# circuit_de_charge.net
KiCad netlist of a schematic drawn in Altium Designer
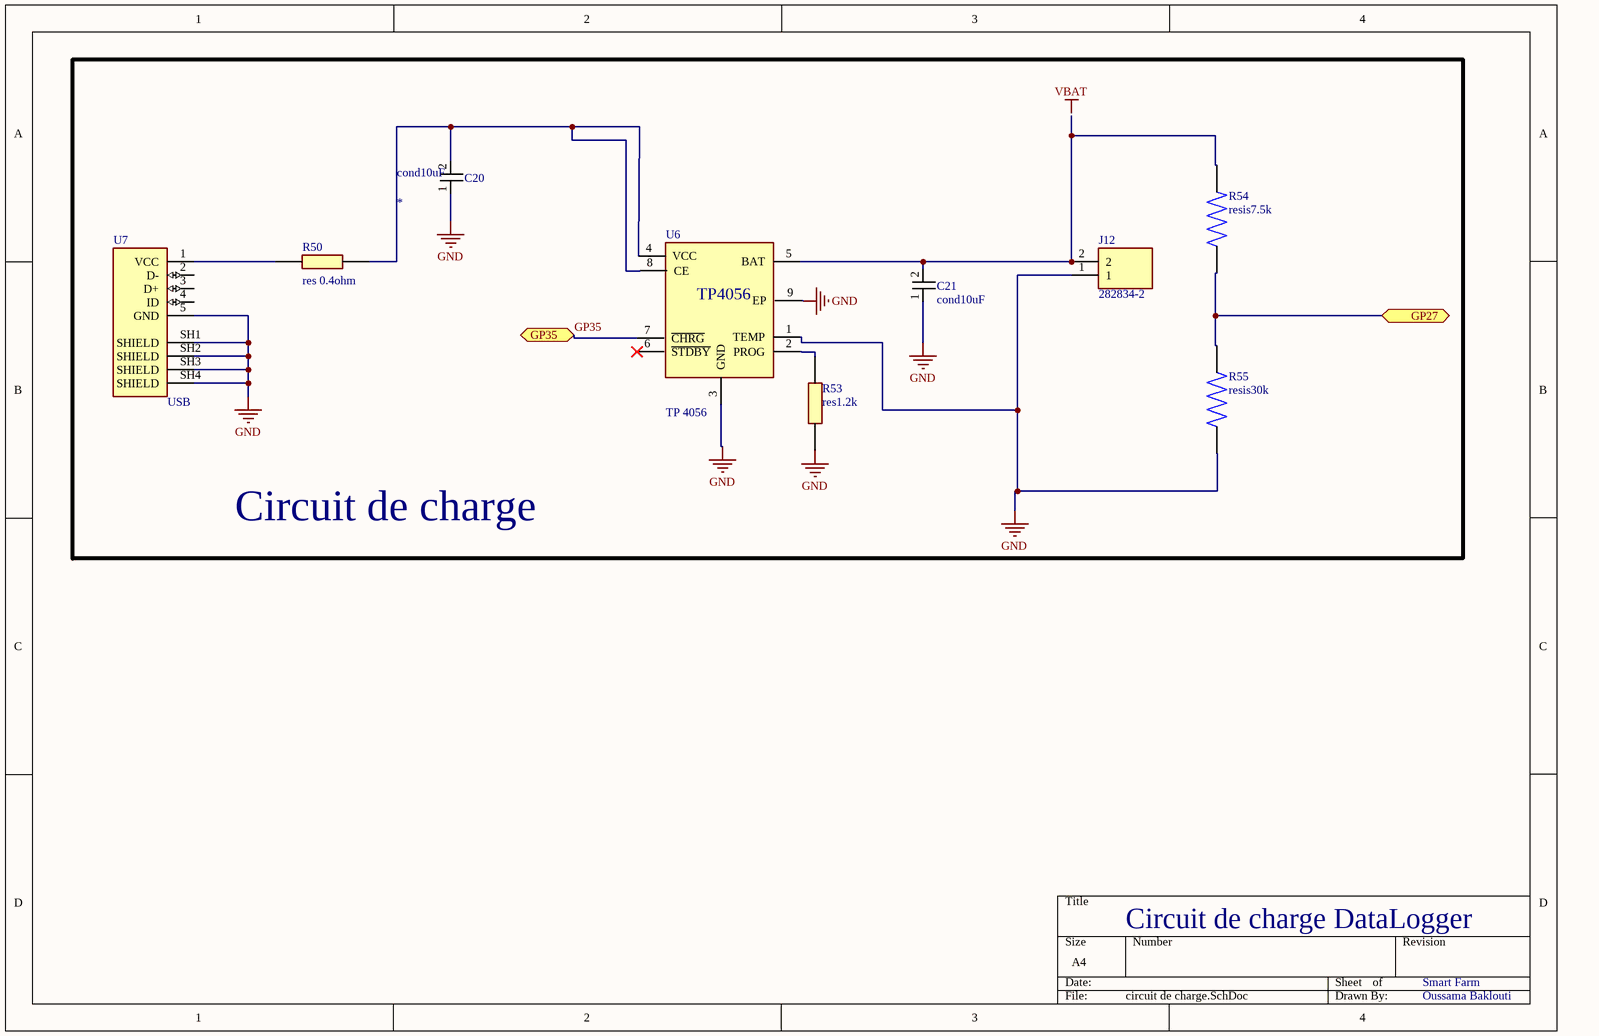
[diagram p0: circuit de charge.SchDoc]

(export (version "E")
  (design (tool "Eeschema 10.0.6"))
  (components
    (comp (ref "C20")
      (value "cond10uF")
      (footprint "cond10uF")
      (description "Multilayer Ceramic Capacitors MLCC - SMD/SMT 16V 10uF X7R 1206 10% AEC-Q200")
      (fields (field (name "MFR") "KYOCERA AVX") (field (name "PARAMETER 1") "*"))
      (libsource (lib "Data_logger") (part "cond10uF"))
    )
    (comp (ref "C21")
      (value "cond10uF")
      (footprint "cond10uF")
      (libsource (lib "Data_logger") (part "cond10uF"))
    )
    (comp (ref "J12")
      (value "282834-2")
      (footprint "282834-2")
      (libsource (lib "Data_logger") (part "282834-2"))
    )
    (comp (ref "R50") (value "~") (footprint "res0.4") (libsource (lib "Data_logger") (part "res0.4")))
    (comp (ref "R53")
      (value "res1.2k")
      (footprint "res1.2k")
      (libsource (lib "Data_logger") (part "res1.2k"))
    )
    (comp (ref "R54")
      (value "resis7.5k")
      (footprint "res7.5k")
      (fields (field (name "MFR") "YAGEO"))
      (libsource (lib "Data_logger") (part "resis7.5k"))
    )
    (comp (ref "R55")
      (value "resis30k")
      (footprint "res30k")
      (fields (field (name "MFR") "YAGEO"))
      (libsource (lib "Data_logger") (part "resis33k"))
    )
    (comp (ref "U6") (value "TP 4056") (footprint "TP4056") (libsource (lib "Data_logger") (part "TP 4056")))
    (comp (ref "U7")
      (value "~")
      (footprint "USB")
      (description "USB - micro B USB 2.0 Receptacle Connector 5 Position Surface Mount, Right Angle")
      (fields (field (name "MFR") "Amphenol ICC (FCI)"))
      (libsource (lib "Data_logger") (part "USB"))
    )
  )
  (nets
    (net (code "1") (name "/GP27") (class "Default")
      (node (ref "R54") (pin "1") (pinfunction "1_1") (pintype "passive"))
      (node (ref "R55") (pin "2") (pinfunction "2_2") (pintype "passive"))
    )
    (net (code "2") (name "/GP35") (class "Default")
      (node (ref "U6") (pin "7") (pinfunction "~{CHRG}_7") (pintype "passive"))
    )
    (net (code "3") (name "GND") (class "Default")
      (node (ref "C20") (pin "1") (pinfunction "1_1") (pintype "passive"))
      (node (ref "C21") (pin "1") (pinfunction "1_1") (pintype "passive"))
      (node (ref "J12") (pin "1") (pinfunction "1_1") (pintype "passive"))
      (node (ref "R53") (pin "1") (pinfunction "1_1") (pintype "passive"))
      (node (ref "R55") (pin "1") (pinfunction "1_1") (pintype "passive"))
      (node (ref "U6") (pin "1") (pinfunction "TEMP_1") (pintype "passive"))
      (node (ref "U6") (pin "3") (pinfunction "GND_3") (pintype "power_in"))
      (node (ref "U6") (pin "9") (pinfunction "EP_9") (pintype "passive"))
      (node (ref "U7") (pin "5") (pinfunction "GND_5") (pintype "power_in"))
      (node (ref "U7") (pin "SH1") (pinfunction "SHIELD_SH1") (pintype "passive"))
      (node (ref "U7") (pin "SH2") (pinfunction "SHIELD_SH2") (pintype "passive"))
      (node (ref "U7") (pin "SH3") (pinfunction "SHIELD_SH3") (pintype "passive"))
      (node (ref "U7") (pin "SH4") (pinfunction "SHIELD_SH4") (pintype "passive"))
    )
    (net (code "4") (name "Net-(U6-BAT)") (class "Default")
      (node (ref "C21") (pin "2") (pinfunction "2_2") (pintype "passive"))
      (node (ref "J12") (pin "2") (pinfunction "2_2") (pintype "passive"))
      (node (ref "R54") (pin "2") (pinfunction "2_2") (pintype "passive"))
      (node (ref "U6") (pin "5") (pinfunction "BAT_5") (pintype "passive"))
    )
    (net (code "5") (name "Net-(U6-CE)") (class "Default")
      (node (ref "C20") (pin "2") (pinfunction "2_2") (pintype "passive"))
      (node (ref "R50") (pin "2") (pinfunction "2_2") (pintype "passive"))
      (node (ref "U6") (pin "4") (pinfunction "VCC_4") (pintype "power_in"))
      (node (ref "U6") (pin "8") (pinfunction "CE_8") (pintype "passive"))
    )
    (net (code "6") (name "Net-(U6-PROG)") (class "Default")
      (node (ref "R53") (pin "2") (pinfunction "2_2") (pintype "passive"))
      (node (ref "U6") (pin "2") (pinfunction "PROG_2") (pintype "passive"))
    )
    (net (code "7") (name "Net-(U7-VCC)") (class "Default")
      (node (ref "R50") (pin "1") (pinfunction "1_1") (pintype "passive"))
      (node (ref "U7") (pin "1") (pinfunction "VCC_1") (pintype "power_in"))
    )
    (net (code "9") (name "unconnected-(U6-~{STDBY}-Pad6)") (class "Default")
      (node (ref "U6") (pin "6") (pinfunction "~{STDBY}_6") (pintype "passive+no_connect"))
    )
    (net (code "10") (name "unconnected-(U7-D+-Pad3)") (class "Default")
      (node (ref "U7") (pin "3") (pinfunction "D+_3") (pintype "bidirectional"))
    )
    (net (code "11") (name "unconnected-(U7-D--Pad2)") (class "Default")
      (node (ref "U7") (pin "2") (pinfunction "D-_2") (pintype "bidirectional"))
    )
    (net (code "12") (name "unconnected-(U7-ID-Pad4)") (class "Default")
      (node (ref "U7") (pin "4") (pinfunction "ID_4") (pintype "bidirectional"))
    )
  )
)
